# connectors_to_BMS_master.net
KiCad netlist of a schematic drawn in Altium Designer
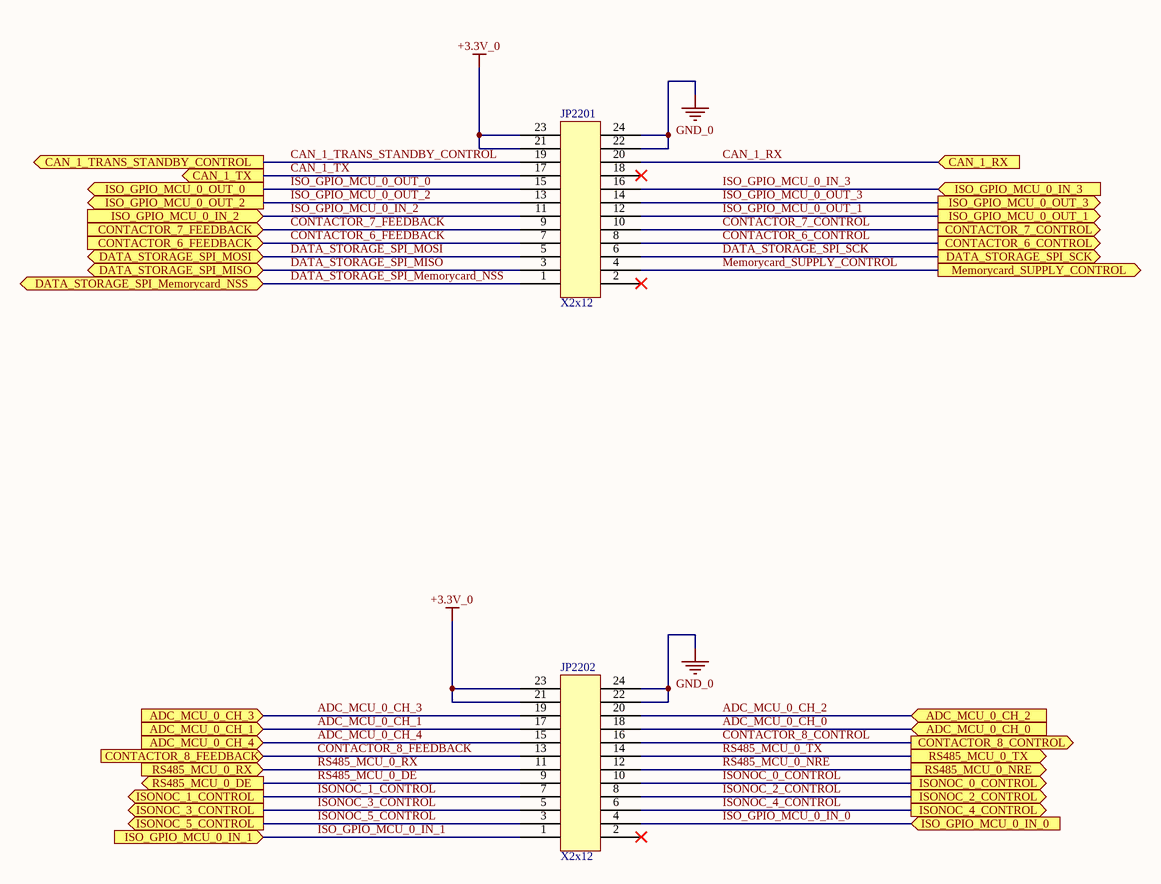
[diagram p0: connectors_to_BMS_master.SchDoc]

(export (version "E")
  (design (tool "Eeschema 10.0.6"))
  (components
    (comp (ref "JP2201")
      (value "X2x12")
      (footprint "Pinheader_2.54_2x12")
      (fields (field (name "PART NUMBER") "samtec_TLW-112-06-G-D") (field (name "MANUFACTURER") "Samtec"))
      (libsource (lib "OE750") (part "X2x12"))
    )
    (comp (ref "JP2202")
      (value "X2x12")
      (footprint "Pinheader_2.54_2x12")
      (fields (field (name "PART NUMBER") "samtec_TLW-112-06-G-D") (field (name "MANUFACTURER") "Samtec"))
      (libsource (lib "OE750") (part "X2x12"))
    )
  )
  (nets
    (net (code "1") (name "+3.3V_0") (class "Default")
      (node (ref "JP2201") (pin "21") (pintype "passive"))
      (node (ref "JP2201") (pin "23") (pintype "passive"))
      (node (ref "JP2202") (pin "21") (pintype "passive"))
      (node (ref "JP2202") (pin "23") (pintype "passive"))
    )
    (net (code "2") (name "/ADC_MCU_0_CH_0") (class "Default")
      (node (ref "JP2202") (pin "18") (pintype "passive"))
    )
    (net (code "3") (name "/ADC_MCU_0_CH_1") (class "Default")
      (node (ref "JP2202") (pin "17") (pintype "passive"))
    )
    (net (code "4") (name "/ADC_MCU_0_CH_2") (class "Default")
      (node (ref "JP2202") (pin "20") (pintype "passive"))
    )
    (net (code "5") (name "/ADC_MCU_0_CH_3") (class "Default")
      (node (ref "JP2202") (pin "19") (pintype "passive"))
    )
    (net (code "6") (name "/ADC_MCU_0_CH_4") (class "Default")
      (node (ref "JP2202") (pin "15") (pintype "passive"))
    )
    (net (code "7") (name "/CAN_1_RX") (class "Default") (node (ref "JP2201") (pin "20") (pintype "passive")))
    (net (code "8") (name "/CAN_1_TRANS_STANDBY_CONTROL") (class "Default")
      (node (ref "JP2201") (pin "19") (pintype "passive"))
    )
    (net (code "9") (name "/CAN_1_TX") (class "Default") (node (ref "JP2201") (pin "17") (pintype "passive")))
    (net (code "10") (name "/CONTACTOR_6_CONTROL") (class "Default")
      (node (ref "JP2201") (pin "8") (pintype "passive"))
    )
    (net (code "11") (name "/CONTACTOR_6_FEEDBACK") (class "Default")
      (node (ref "JP2201") (pin "7") (pintype "passive"))
    )
    (net (code "12") (name "/CONTACTOR_7_CONTROL") (class "Default")
      (node (ref "JP2201") (pin "10") (pintype "passive"))
    )
    (net (code "13") (name "/CONTACTOR_7_FEEDBACK") (class "Default")
      (node (ref "JP2201") (pin "9") (pintype "passive"))
    )
    (net (code "14") (name "/CONTACTOR_8_CONTROL") (class "Default")
      (node (ref "JP2202") (pin "16") (pintype "passive"))
    )
    (net (code "15") (name "/CONTACTOR_8_FEEDBACK") (class "Default")
      (node (ref "JP2202") (pin "13") (pintype "passive"))
    )
    (net (code "16") (name "/DATA_STORAGE_SPI_MISO") (class "Default")
      (node (ref "JP2201") (pin "3") (pintype "passive"))
    )
    (net (code "17") (name "/DATA_STORAGE_SPI_MOSI") (class "Default")
      (node (ref "JP2201") (pin "5") (pintype "passive"))
    )
    (net (code "18") (name "/DATA_STORAGE_SPI_Memorycard_NSS") (class "Default")
      (node (ref "JP2201") (pin "1") (pintype "passive"))
    )
    (net (code "19") (name "/DATA_STORAGE_SPI_SCK") (class "Default")
      (node (ref "JP2201") (pin "6") (pintype "passive"))
    )
    (net (code "20") (name "/ISONOC_0_CONTROL") (class "Default")
      (node (ref "JP2202") (pin "10") (pintype "passive"))
    )
    (net (code "21") (name "/ISONOC_1_CONTROL") (class "Default")
      (node (ref "JP2202") (pin "7") (pintype "passive"))
    )
    (net (code "22") (name "/ISONOC_2_CONTROL") (class "Default")
      (node (ref "JP2202") (pin "8") (pintype "passive"))
    )
    (net (code "23") (name "/ISONOC_3_CONTROL") (class "Default")
      (node (ref "JP2202") (pin "5") (pintype "passive"))
    )
    (net (code "24") (name "/ISONOC_4_CONTROL") (class "Default")
      (node (ref "JP2202") (pin "6") (pintype "passive"))
    )
    (net (code "25") (name "/ISONOC_5_CONTROL") (class "Default")
      (node (ref "JP2202") (pin "3") (pintype "passive"))
    )
    (net (code "26") (name "/ISO_GPIO_MCU_0_IN_0") (class "Default")
      (node (ref "JP2202") (pin "4") (pintype "passive"))
    )
    (net (code "27") (name "/ISO_GPIO_MCU_0_IN_1") (class "Default")
      (node (ref "JP2202") (pin "1") (pintype "passive"))
    )
    (net (code "28") (name "/ISO_GPIO_MCU_0_IN_2") (class "Default")
      (node (ref "JP2201") (pin "11") (pintype "passive"))
    )
    (net (code "29") (name "/ISO_GPIO_MCU_0_IN_3") (class "Default")
      (node (ref "JP2201") (pin "16") (pintype "passive"))
    )
    (net (code "30") (name "/ISO_GPIO_MCU_0_OUT_0") (class "Default")
      (node (ref "JP2201") (pin "15") (pintype "passive"))
    )
    (net (code "31") (name "/ISO_GPIO_MCU_0_OUT_1") (class "Default")
      (node (ref "JP2201") (pin "12") (pintype "passive"))
    )
    (net (code "32") (name "/ISO_GPIO_MCU_0_OUT_2") (class "Default")
      (node (ref "JP2201") (pin "13") (pintype "passive"))
    )
    (net (code "33") (name "/ISO_GPIO_MCU_0_OUT_3") (class "Default")
      (node (ref "JP2201") (pin "14") (pintype "passive"))
    )
    (net (code "34") (name "/Memorycard_SUPPLY_CONTROL") (class "Default")
      (node (ref "JP2201") (pin "4") (pintype "passive"))
    )
    (net (code "35") (name "/RS485_MCU_0_DE") (class "Default")
      (node (ref "JP2202") (pin "9") (pintype "passive"))
    )
    (net (code "36") (name "/RS485_MCU_0_NRE") (class "Default")
      (node (ref "JP2202") (pin "12") (pintype "passive"))
    )
    (net (code "37") (name "/RS485_MCU_0_RX") (class "Default")
      (node (ref "JP2202") (pin "11") (pintype "passive"))
    )
    (net (code "38") (name "/RS485_MCU_0_TX") (class "Default")
      (node (ref "JP2202") (pin "14") (pintype "passive"))
    )
    (net (code "39") (name "GND_0") (class "Default")
      (node (ref "JP2201") (pin "22") (pintype "passive"))
      (node (ref "JP2201") (pin "24") (pintype "passive"))
      (node (ref "JP2202") (pin "22") (pintype "passive"))
      (node (ref "JP2202") (pin "24") (pintype "passive"))
    )
    (net (code "40") (name "unconnected-(JP2201-Pad2)") (class "Default")
      (node (ref "JP2201") (pin "2") (pintype "passive+no_connect"))
    )
    (net (code "41") (name "unconnected-(JP2201-Pad18)") (class "Default")
      (node (ref "JP2201") (pin "18") (pintype "passive+no_connect"))
    )
    (net (code "42") (name "unconnected-(JP2202-Pad2)") (class "Default")
      (node (ref "JP2202") (pin "2") (pintype "passive+no_connect"))
    )
  )
)
